# MT-SWD_V1_0.net
KiCad netlist of a schematic drawn in Altium Designer
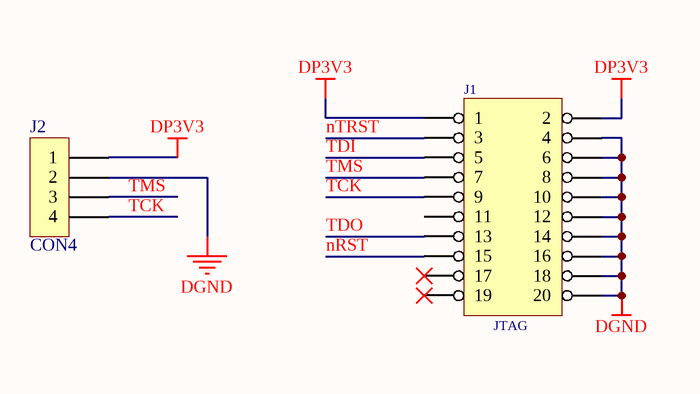
[diagram p0: MT-SWD V1.0.SchDoc]

(export (version "E")
  (design (tool "Eeschema 10.0.6"))
  (components
    (comp (ref "J1") (value "JTAG") (footprint "FH12-10S-1SH") (libsource (lib "*") (part "HEADER 10X2")))
    (comp (ref "J2")
      (value "CON4")
      (footprint "COM4-2.54mm-90")
      (description "Connector")
      (libsource (lib "Mini9") (part "CON4"))
    )
  )
  (nets
    (net (code "1") (name "/TCK") (class "Default")
      (node (ref "J1") (pin "9") (pinfunction "9_9") (pintype "passive"))
      (node (ref "J2") (pin "4") (pinfunction "4_4") (pintype "passive"))
    )
    (net (code "2") (name "/TDI") (class "Default")
      (node (ref "J1") (pin "5") (pinfunction "5_5") (pintype "passive"))
    )
    (net (code "3") (name "/TDO") (class "Default")
      (node (ref "J1") (pin "13") (pinfunction "13_13") (pintype "passive"))
    )
    (net (code "4") (name "/TMS") (class "Default")
      (node (ref "J1") (pin "7") (pinfunction "7_7") (pintype "passive"))
      (node (ref "J2") (pin "3") (pinfunction "3_3") (pintype "passive"))
    )
    (net (code "5") (name "/nRST") (class "Default")
      (node (ref "J1") (pin "15") (pinfunction "15_15") (pintype "passive"))
    )
    (net (code "6") (name "/nTRST") (class "Default")
      (node (ref "J1") (pin "3") (pinfunction "3_3") (pintype "passive"))
    )
    (net (code "7") (name "DGND") (class "Default")
      (node (ref "J1") (pin "10") (pinfunction "10_10") (pintype "passive"))
      (node (ref "J1") (pin "12") (pinfunction "12_12") (pintype "passive"))
      (node (ref "J1") (pin "14") (pinfunction "14_14") (pintype "passive"))
      (node (ref "J1") (pin "16") (pinfunction "16_16") (pintype "passive"))
      (node (ref "J1") (pin "18") (pinfunction "18_18") (pintype "passive"))
      (node (ref "J1") (pin "20") (pinfunction "20_20") (pintype "passive"))
      (node (ref "J1") (pin "4") (pinfunction "4_4") (pintype "passive"))
      (node (ref "J1") (pin "6") (pinfunction "6_6") (pintype "passive"))
      (node (ref "J1") (pin "8") (pinfunction "8_8") (pintype "passive"))
      (node (ref "J2") (pin "2") (pinfunction "2_2") (pintype "passive"))
    )
    (net (code "8") (name "DP3V3") (class "Default")
      (node (ref "J1") (pin "1") (pinfunction "1_1") (pintype "passive"))
      (node (ref "J1") (pin "2") (pinfunction "2_2") (pintype "passive"))
      (node (ref "J2") (pin "1") (pinfunction "1_1") (pintype "passive"))
    )
    (net (code "9") (name "unconnected-(J1-Pad11)") (class "Default")
      (node (ref "J1") (pin "11") (pinfunction "11_11") (pintype "passive"))
    )
    (net (code "10") (name "unconnected-(J1-Pad17)") (class "Default")
      (node (ref "J1") (pin "17") (pinfunction "17_17") (pintype "passive+no_connect"))
    )
    (net (code "11") (name "unconnected-(J1-Pad19)") (class "Default")
      (node (ref "J1") (pin "19") (pinfunction "19_19") (pintype "passive+no_connect"))
    )
  )
)
